# Gate_Driver_2.net
KiCad netlist of a schematic drawn in Altium Designer
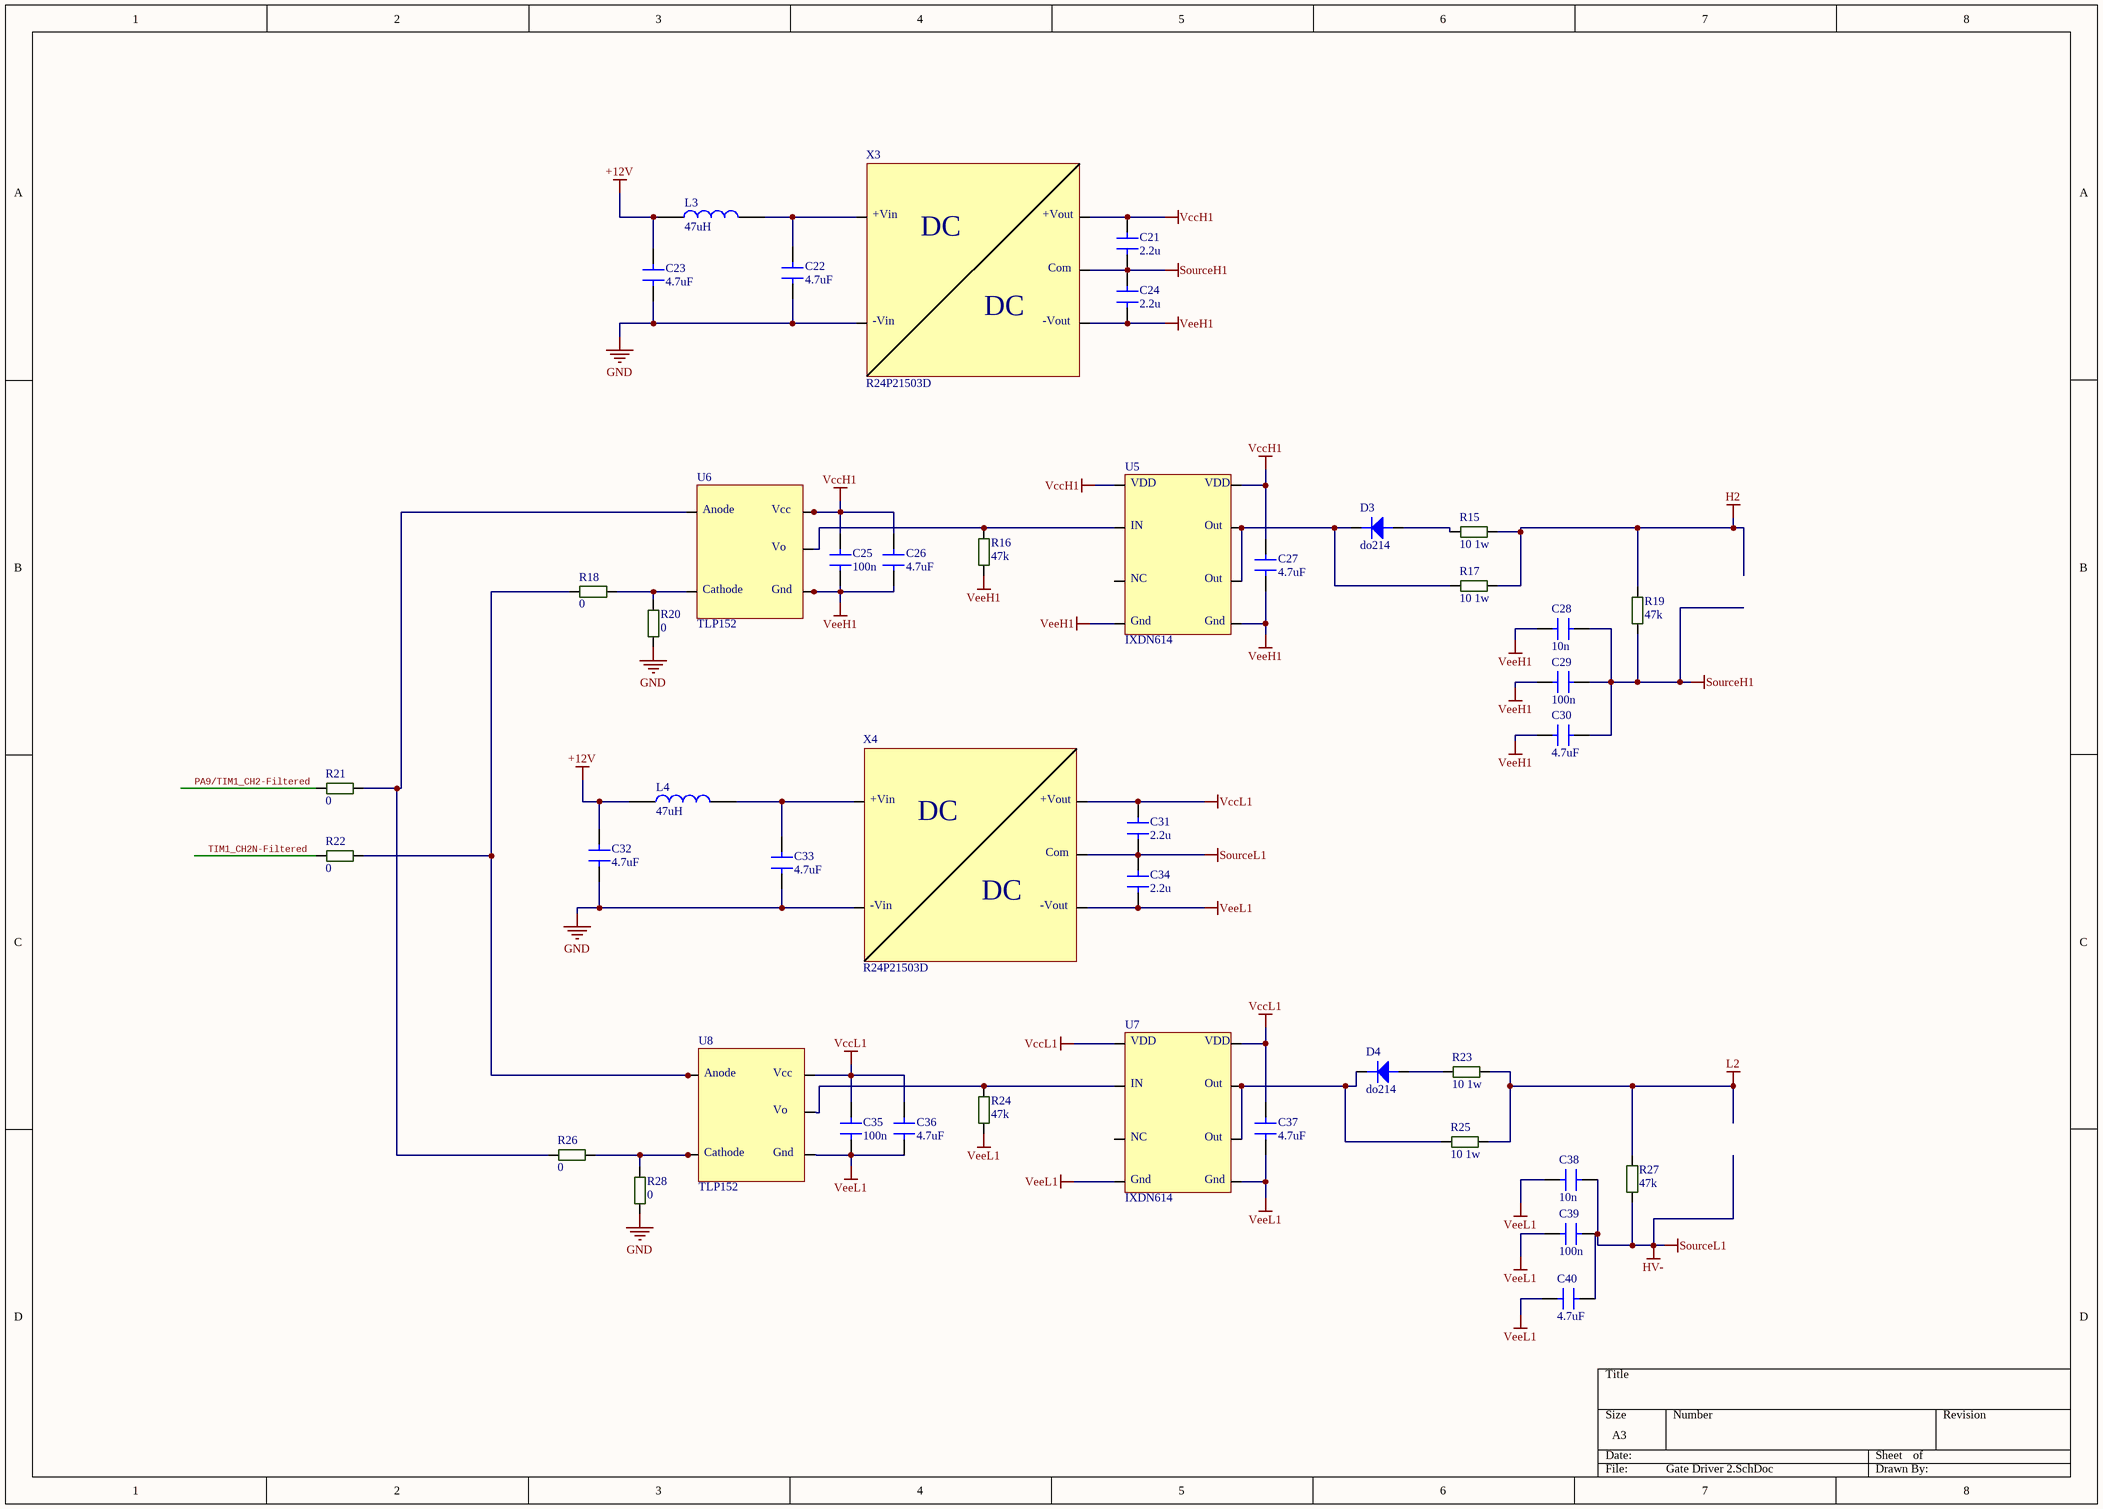
[diagram p0: Gate Driver 2.SchDoc]

(export (version "E")
  (design (tool "Eeschema 10.0.6"))
  (components
    (comp (ref "C21")
      (value "2.2u")
      (footprint "C-0805")
      (libsource (lib "Gate Driver Board") (part "C-0805"))
    )
    (comp (ref "C22")
      (value "4.7uF")
      (footprint "C-1206")
      (description "Cap1206 4.7uF")
      (fields (field (name "ÖZDISAN PART NUMBER") "CL31B475KBHNNNE") (field (name "MANUFACTURER") "SAMSUNG"))
      (libsource (lib "Gate Driver Board") (part "Cap1206"))
    )
    (comp (ref "C23")
      (value "4.7uF")
      (footprint "C-1206")
      (description "Cap1206 4.7uF")
      (fields (field (name "ÖZDISAN PART NUMBER") "CL31B475KBHNNNE") (field (name "MANUFACTURER") "SAMSUNG"))
      (libsource (lib "Gate Driver Board") (part "Cap1206"))
    )
    (comp (ref "C24")
      (value "2.2u")
      (footprint "C-0805")
      (libsource (lib "Gate Driver Board") (part "C-0805"))
    )
    (comp (ref "C25")
      (value "100n")
      (footprint "C-0805")
      (libsource (lib "Gate Driver Board") (part "C-0805"))
    )
    (comp (ref "C26")
      (value "4.7uF")
      (footprint "C-1206")
      (description "Cap1206 4.7uF")
      (libsource (lib "Gate Driver Board") (part "C-1206"))
    )
    (comp (ref "C27")
      (value "4.7uF")
      (footprint "C-1206")
      (description "Cap1206 4.7uF")
      (libsource (lib "Gate Driver Board") (part "C-1206"))
    )
    (comp (ref "C28")
      (value "10n")
      (footprint "C-0805")
      (libsource (lib "Gate Driver Board") (part "C-0805"))
    )
    (comp (ref "C29")
      (value "100n")
      (footprint "C-0805")
      (libsource (lib "Gate Driver Board") (part "C-0805"))
    )
    (comp (ref "C30")
      (value "4.7uF")
      (footprint "C-1206")
      (description "Cap1206 4.7uF")
      (fields (field (name "ÖZDISAN PART NUMBER") " CL31B475KBHNNNE") (field (name "MANUFACTURER") "SAMSUNG"))
      (libsource (lib "Gate Driver Board") (part "Cap1206"))
    )
    (comp (ref "C31")
      (value "2.2u")
      (footprint "C-0805")
      (libsource (lib "Gate Driver Board") (part "C-0805"))
    )
    (comp (ref "C32")
      (value "4.7uF")
      (footprint "C-1206")
      (description "Cap1206 4.7uF")
      (fields (field (name "ÖZDISAN PART NUMBER") "CL31B475KBHNNNE") (field (name "MANUFACTURER") "SAMSUNG"))
      (libsource (lib "Gate Driver Board") (part "Cap1206"))
    )
    (comp (ref "C33")
      (value "4.7uF")
      (footprint "C-1206")
      (description "Cap1206 4.7uF")
      (fields (field (name "ÖZDISAN PART NUMBER") " CL31B475KBHNNNE") (field (name "MANUFACTURER") "SAMSUNG"))
      (libsource (lib "Gate Driver Board") (part "Cap1206"))
    )
    (comp (ref "C34")
      (value "2.2u")
      (footprint "C-0805")
      (libsource (lib "Gate Driver Board") (part "C-0805"))
    )
    (comp (ref "C35")
      (value "100n")
      (footprint "C-0805")
      (libsource (lib "Gate Driver Board") (part "C-0805"))
    )
    (comp (ref "C36")
      (value "4.7uF")
      (footprint "C-1206")
      (description "Cap1206 4.7uF")
      (libsource (lib "Gate Driver Board") (part "C-1206"))
    )
    (comp (ref "C37")
      (value "4.7uF")
      (footprint "C-1206")
      (description "Cap1206 4.7uF")
      (libsource (lib "Gate Driver Board") (part "C-1206"))
    )
    (comp (ref "C38")
      (value "10n")
      (footprint "C-0805")
      (libsource (lib "Gate Driver Board") (part "C-0805"))
    )
    (comp (ref "C39")
      (value "100n")
      (footprint "C-0805")
      (libsource (lib "Gate Driver Board") (part "C-0805"))
    )
    (comp (ref "C40")
      (value "4.7uF")
      (footprint "C-1206")
      (description "Cap1206 4.7uF")
      (fields (field (name "ÖZDISAN PART NUMBER") "CL31B475KBHNNNE") (field (name "MANUFACTURER") "SAMSUNG"))
      (libsource (lib "Gate Driver Board") (part "Cap1206"))
    )
    (comp (ref "D3")
      (value "do214")
      (footprint "DO-214AC")
      (description "DIODE FAST SWITCHING Single 150mA 75V SMT SOD323")
      (libsource (lib "Gate Driver Board") (part "do214"))
    )
    (comp (ref "D4")
      (value "do214")
      (footprint "DO-214AC")
      (description "DIODE FAST SWITCHING Single 150mA 75V SMT SOD323")
      (libsource (lib "Gate Driver Board") (part "do214"))
    )
    (comp (ref "L3")
      (value "47uH")
      (footprint "WE-TPC_282892")
      (libsource (lib "Gate Driver Board") (part "inductor"))
    )
    (comp (ref "L4")
      (value "47uH")
      (footprint "WE-TPC_282892")
      (libsource (lib "Gate Driver Board") (part "inductor"))
    )
    (comp (ref "R15")
      (value "10 1w")
      (footprint "R-2512")
      (description "R-2512 10R 1W")
      (libsource (lib "Gate Driver Board") (part "R-2512"))
    )
    (comp (ref "R16")
      (value "47k")
      (footprint "R-0805")
      (description "RES.(2012) 0805 47K Ohms 5% 1/8W-S 100PPM")
      (fields (field (name "MANUFACTURER") "ROYALOHM") (field (name "ÖZDISAN PART NUMBER") "0805S8J0473T5E"))
      (libsource (lib "Gate Driver Board") (part "Res0805"))
    )
    (comp (ref "R17")
      (value "10 1w")
      (footprint "R-2512")
      (description "R-2512 10R 1W")
      (libsource (lib "Gate Driver Board") (part "R-2512"))
    )
    (comp (ref "R18")
      (value "0")
      (footprint "R-0805")
      (description "Res0805 0R")
      (fields (field (name "MANUFACTURER") "ROYALOHM") (field (name "ÖZDISAN PART NUMBER") "0805S8J0000T5E"))
      (libsource (lib "Gate Driver Board") (part "Res0805"))
    )
    (comp (ref "R19")
      (value "47k")
      (footprint "R-0805")
      (description "RES.(2012) 0805 47K Ohms 5% 1/8W-S 100PPM")
      (fields (field (name "ÖZDISAN PART NUMBER") "0805S8J0473T5E") (field (name "MANUFACTURER") "ROYALOHM"))
      (libsource (lib "Gate Driver Board") (part "Res0805"))
    )
    (comp (ref "R20")
      (value "0")
      (footprint "R-0805")
      (description "Res0805 0R")
      (fields (field (name "MANUFACTURER") "ROYALOHM") (field (name "ÖZDISAN PART NUMBER") "0805S8J0000T5E"))
      (libsource (lib "Gate Driver Board") (part "Res0805"))
    )
    (comp (ref "R21")
      (value "0")
      (footprint "R-0805")
      (description "Res0805 0R")
      (fields (field (name "MANUFACTURER") "ROYALOHM") (field (name "ÖZDISAN PART NUMBER") "0805S8J0000T5E"))
      (libsource (lib "Gate Driver Board") (part "Res0805"))
    )
    (comp (ref "R22")
      (value "0")
      (footprint "R-0805")
      (description "Res0805 0R")
      (fields (field (name "MANUFACTURER") "ROYALOHM") (field (name "ÖZDISAN PART NUMBER") "0805S8J0000T5E"))
      (libsource (lib "Gate Driver Board") (part "Res0805"))
    )
    (comp (ref "R23")
      (value "10 1w")
      (footprint "R-2512")
      (description "R-2512 10R 1W")
      (libsource (lib "Gate Driver Board") (part "R-2512"))
    )
    (comp (ref "R24")
      (value "47k")
      (footprint "R-0805")
      (description "RES.(2012) 0805 47K Ohms 5% 1/8W-S 100PPM")
      (fields (field (name "ÖZDISAN PART NUMBER") "0805S8J0473T5E") (field (name "MANUFACTURER") "ROYALOHM"))
      (libsource (lib "Gate Driver Board") (part "Res0805"))
    )
    (comp (ref "R25")
      (value "10 1w")
      (footprint "R-2512")
      (description "R-2512 10R 1W")
      (libsource (lib "Gate Driver Board") (part "R-2512"))
    )
    (comp (ref "R26")
      (value "0")
      (footprint "R-0805")
      (description "Res0805 0R")
      (fields (field (name "MANUFACTURER") "ROYALOHM") (field (name "ÖZDISAN PART NUMBER") "0805S8J0000T5E"))
      (libsource (lib "Gate Driver Board") (part "Res0805"))
    )
    (comp (ref "R27")
      (value "47k")
      (footprint "R-0805")
      (description "RES.(2012) 0805 47K Ohms 5% 1/8W-S 100PPM")
      (fields (field (name "ÖZDISAN PART NUMBER") "0805S8J0473T5E") (field (name "MANUFACTURER") "ROYALOHM"))
      (libsource (lib "Gate Driver Board") (part "Res0805"))
    )
    (comp (ref "R28")
      (value "0")
      (footprint "R-0805")
      (description "Res0805 0R")
      (fields (field (name "MANUFACTURER") "ROYALOHM") (field (name "ÖZDISAN PART NUMBER") "0805S8J0000T5E"))
      (libsource (lib "Gate Driver Board") (part "Res0805"))
    )
    (comp (ref "U5")
      (value "IXDN614")
      (footprint "FAN3122 Soic8")
      (description "14A 8SOIC EXP MTL NON INVERTING")
      (fields
        (field (name "MANUFACTURER") "Ixys Clare")
        (field (name "MANUFACTURER PART NUMBER") "IXDN614SITR")
      )
      (libsource (lib "Gate Driver Board") (part "IXDN614SITR"))
    )
    (comp (ref "U6")
      (value "TLP152")
      (footprint "TLP152")
      (description "OPTOISO 3.75KV GATE DRIVER 6SO-5")
      (fields
        (field (name "MANUFACTURER") "Toshiba")
        (field (name "MANUFACTURER PART NUMBER") "TLP152(TPL,E")
      )
      (libsource (lib "Gate Driver Board") (part "TLP152(TPL,E"))
    )
    (comp (ref "U7")
      (value "IXDN614")
      (footprint "FAN3122 Soic8")
      (description "14A 8SOIC EXP MTL NON INVERTING")
      (fields
        (field (name "MANUFACTURER") "Ixys Clare")
        (field (name "MANUFACTURER PART NUMBER") "IXDN614SITR")
      )
      (libsource (lib "Gate Driver Board") (part "IXDN614SITR"))
    )
    (comp (ref "U8")
      (value "TLP152")
      (footprint "TLP152")
      (description "OPTOISO 3.75KV GATE DRIVER 6SO-5")
      (fields
        (field (name "MANUFACTURER") "Toshiba")
        (field (name "MANUFACTURER PART NUMBER") "TLP152(TPL,E")
      )
      (libsource (lib "Gate Driver Board") (part "TLP152(TPL,E"))
    )
    (comp (ref "X3")
      (value "R24P21503D")
      (footprint "SIP7")
      (fields (field (name "MANUFACTURER") "Recom"))
      (libsource (lib "Gate Driver Board") (part "R24P21503D"))
    )
    (comp (ref "X4")
      (value "R24P21503D")
      (footprint "SIP7")
      (fields (field (name "MANUFACTURER") "Recom"))
      (libsource (lib "Gate Driver Board") (part "R24P21503D"))
    )
  )
  (nets
    (net (code "1") (name "+12V") (class "Default")
      (node (ref "C23") (pin "2") (pinfunction "2_2") (pintype "passive"))
      (node (ref "C32") (pin "2") (pinfunction "2_2") (pintype "passive"))
      (node (ref "L3") (pin "1") (pinfunction "1_1") (pintype "passive"))
      (node (ref "L4") (pin "1") (pinfunction "1_1") (pintype "passive"))
    )
    (net (code "2") (name "/PA9{slash}TIM1_CH2-Filtered") (class "Default")
      (node (ref "R21") (pin "1") (pinfunction "1_1") (pintype "passive"))
    )
    (net (code "3") (name "/TIM1_CH2N-Filtered") (class "Default")
      (node (ref "R22") (pin "1") (pinfunction "1_1") (pintype "passive"))
    )
    (net (code "4") (name "GND") (class "Default")
      (node (ref "C22") (pin "1") (pinfunction "1_1") (pintype "passive"))
      (node (ref "C23") (pin "1") (pinfunction "1_1") (pintype "passive"))
      (node (ref "C32") (pin "1") (pinfunction "1_1") (pintype "passive"))
      (node (ref "C33") (pin "1") (pinfunction "1_1") (pintype "passive"))
      (node (ref "R20") (pin "1") (pinfunction "1_1") (pintype "passive"))
      (node (ref "R28") (pin "1") (pinfunction "1_1") (pintype "passive"))
      (node (ref "X3") (pin "2") (pinfunction "2_2") (pintype "passive"))
      (node (ref "X4") (pin "2") (pinfunction "2_2") (pintype "passive"))
    )
    (net (code "5") (name "H2") (class "Default")
      (node (ref "R15") (pin "2") (pinfunction "2_2") (pintype "passive"))
      (node (ref "R17") (pin "2") (pinfunction "2_2") (pintype "passive"))
      (node (ref "R19") (pin "2") (pinfunction "2_2") (pintype "passive"))
    )
    (net (code "6") (name "HV-") (class "Default")
      (node (ref "C31") (pin "1") (pinfunction "1_1") (pintype "passive"))
      (node (ref "C34") (pin "2") (pinfunction "2_2") (pintype "passive"))
      (node (ref "C38") (pin "1") (pinfunction "1_1") (pintype "passive"))
      (node (ref "C39") (pin "1") (pinfunction "1_1") (pintype "passive"))
      (node (ref "C40") (pin "2") (pinfunction "2_2") (pintype "passive"))
      (node (ref "R27") (pin "1") (pinfunction "1_1") (pintype "passive"))
      (node (ref "X4") (pin "6") (pinfunction "6_6") (pintype "passive"))
    )
    (net (code "7") (name "L2") (class "Default")
      (node (ref "R23") (pin "2") (pinfunction "2_2") (pintype "passive"))
      (node (ref "R25") (pin "2") (pinfunction "2_2") (pintype "passive"))
      (node (ref "R27") (pin "2") (pinfunction "2_2") (pintype "passive"))
    )
    (net (code "8") (name "Net-(C22-Pad2)") (class "Default")
      (node (ref "C22") (pin "2") (pinfunction "2_2") (pintype "passive"))
      (node (ref "L3") (pin "2") (pinfunction "2_2") (pintype "passive"))
      (node (ref "X3") (pin "1") (pinfunction "1_1") (pintype "passive"))
    )
    (net (code "9") (name "Net-(C33-Pad2)") (class "Default")
      (node (ref "C33") (pin "2") (pinfunction "2_2") (pintype "passive"))
      (node (ref "L4") (pin "2") (pinfunction "2_2") (pintype "passive"))
      (node (ref "X4") (pin "1") (pinfunction "1_1") (pintype "passive"))
    )
    (net (code "10") (name "Net-(D3-Pada)") (class "Default")
      (node (ref "D3") (pin "a") (pinfunction "a_a") (pintype "passive"))
      (node (ref "R15") (pin "1") (pinfunction "1_1") (pintype "passive"))
    )
    (net (code "11") (name "Net-(D3-Padk)") (class "Default")
      (node (ref "D3") (pin "k") (pinfunction "k_k") (pintype "passive"))
      (node (ref "R17") (pin "1") (pinfunction "1_1") (pintype "passive"))
      (node (ref "U5") (pin "6") (pinfunction "6_6") (pintype "passive"))
      (node (ref "U5") (pin "7") (pinfunction "7_7") (pintype "passive"))
    )
    (net (code "12") (name "Net-(D4-Pada)") (class "Default")
      (node (ref "D4") (pin "a") (pinfunction "a_a") (pintype "passive"))
      (node (ref "R23") (pin "1") (pinfunction "1_1") (pintype "passive"))
    )
    (net (code "13") (name "Net-(D4-Padk)") (class "Default")
      (node (ref "D4") (pin "k") (pinfunction "k_k") (pintype "passive"))
      (node (ref "R25") (pin "1") (pinfunction "1_1") (pintype "passive"))
      (node (ref "U7") (pin "6") (pinfunction "6_6") (pintype "passive"))
      (node (ref "U7") (pin "7") (pinfunction "7_7") (pintype "passive"))
    )
    (net (code "14") (name "Net-(R16-Pad2)") (class "Default")
      (node (ref "R16") (pin "2") (pinfunction "2_2") (pintype "passive"))
      (node (ref "U5") (pin "2") (pinfunction "2_2") (pintype "passive"))
      (node (ref "U6") (pin "4") (pinfunction "4_4") (pintype "passive"))
    )
    (net (code "15") (name "Net-(R18-Pad1)") (class "Default")
      (node (ref "R18") (pin "1") (pinfunction "1_1") (pintype "passive"))
      (node (ref "R22") (pin "2") (pinfunction "2_2") (pintype "passive"))
      (node (ref "U8") (pin "1") (pinfunction "1_1") (pintype "passive"))
    )
    (net (code "16") (name "Net-(R18-Pad2)") (class "Default")
      (node (ref "R18") (pin "2") (pinfunction "2_2") (pintype "passive"))
      (node (ref "R20") (pin "2") (pinfunction "2_2") (pintype "passive"))
      (node (ref "U6") (pin "2") (pinfunction "2_2") (pintype "passive"))
    )
    (net (code "17") (name "Net-(R21-Pad2)") (class "Default")
      (node (ref "R21") (pin "2") (pinfunction "2_2") (pintype "passive"))
      (node (ref "R26") (pin "1") (pinfunction "1_1") (pintype "passive"))
      (node (ref "U6") (pin "1") (pinfunction "1_1") (pintype "passive"))
    )
    (net (code "18") (name "Net-(R24-Pad2)") (class "Default")
      (node (ref "R24") (pin "2") (pinfunction "2_2") (pintype "passive"))
      (node (ref "U7") (pin "2") (pinfunction "2_2") (pintype "passive"))
      (node (ref "U8") (pin "4") (pinfunction "4_4") (pintype "passive"))
    )
    (net (code "19") (name "Net-(R26-Pad2)") (class "Default")
      (node (ref "R26") (pin "2") (pinfunction "2_2") (pintype "passive"))
      (node (ref "R28") (pin "2") (pinfunction "2_2") (pintype "passive"))
      (node (ref "U8") (pin "2") (pinfunction "2_2") (pintype "passive"))
    )
    (net (code "20") (name "SourceH1") (class "Default")
      (node (ref "C21") (pin "1") (pinfunction "1_1") (pintype "passive"))
      (node (ref "C24") (pin "2") (pinfunction "2_2") (pintype "passive"))
      (node (ref "C28") (pin "1") (pinfunction "1_1") (pintype "passive"))
      (node (ref "C29") (pin "1") (pinfunction "1_1") (pintype "passive"))
      (node (ref "C30") (pin "2") (pinfunction "2_2") (pintype "passive"))
      (node (ref "R19") (pin "1") (pinfunction "1_1") (pintype "passive"))
      (node (ref "X3") (pin "6") (pinfunction "6_6") (pintype "passive"))
    )
    (net (code "21") (name "VccH1") (class "Default")
      (node (ref "C21") (pin "2") (pinfunction "2_2") (pintype "passive"))
      (node (ref "C25") (pin "2") (pinfunction "2_2") (pintype "passive"))
      (node (ref "C26") (pin "2") (pinfunction "2_2") (pintype "passive"))
      (node (ref "C27") (pin "2") (pinfunction "2_2") (pintype "passive"))
      (node (ref "U5") (pin "1") (pinfunction "1_1") (pintype "passive"))
      (node (ref "U5") (pin "8") (pinfunction "8_8") (pintype "passive"))
      (node (ref "U6") (pin "5") (pinfunction "5_5") (pintype "passive"))
      (node (ref "X3") (pin "7") (pinfunction "7_7") (pintype "passive"))
    )
    (net (code "22") (name "VccL1") (class "Default")
      (node (ref "C31") (pin "2") (pinfunction "2_2") (pintype "passive"))
      (node (ref "C35") (pin "2") (pinfunction "2_2") (pintype "passive"))
      (node (ref "C36") (pin "2") (pinfunction "2_2") (pintype "passive"))
      (node (ref "C37") (pin "2") (pinfunction "2_2") (pintype "passive"))
      (node (ref "U7") (pin "1") (pinfunction "1_1") (pintype "passive"))
      (node (ref "U7") (pin "8") (pinfunction "8_8") (pintype "passive"))
      (node (ref "U8") (pin "5") (pinfunction "5_5") (pintype "passive"))
      (node (ref "X4") (pin "7") (pinfunction "7_7") (pintype "passive"))
    )
    (net (code "23") (name "VeeH1") (class "Default")
      (node (ref "C24") (pin "1") (pinfunction "1_1") (pintype "passive"))
      (node (ref "C25") (pin "1") (pinfunction "1_1") (pintype "passive"))
      (node (ref "C26") (pin "1") (pinfunction "1_1") (pintype "passive"))
      (node (ref "C27") (pin "1") (pinfunction "1_1") (pintype "passive"))
      (node (ref "C28") (pin "2") (pinfunction "2_2") (pintype "passive"))
      (node (ref "C29") (pin "2") (pinfunction "2_2") (pintype "passive"))
      (node (ref "C30") (pin "1") (pinfunction "1_1") (pintype "passive"))
      (node (ref "R16") (pin "1") (pinfunction "1_1") (pintype "passive"))
      (node (ref "U5") (pin "4") (pinfunction "4_4") (pintype "passive"))
      (node (ref "U5") (pin "5") (pinfunction "5_5") (pintype "passive"))
      (node (ref "U6") (pin "3") (pinfunction "3_3") (pintype "passive"))
      (node (ref "X3") (pin "5") (pinfunction "5_5") (pintype "passive"))
    )
    (net (code "24") (name "VeeL1") (class "Default")
      (node (ref "C34") (pin "1") (pinfunction "1_1") (pintype "passive"))
      (node (ref "C35") (pin "1") (pinfunction "1_1") (pintype "passive"))
      (node (ref "C36") (pin "1") (pinfunction "1_1") (pintype "passive"))
      (node (ref "C37") (pin "1") (pinfunction "1_1") (pintype "passive"))
      (node (ref "C38") (pin "2") (pinfunction "2_2") (pintype "passive"))
      (node (ref "C39") (pin "2") (pinfunction "2_2") (pintype "passive"))
      (node (ref "C40") (pin "1") (pinfunction "1_1") (pintype "passive"))
      (node (ref "R24") (pin "1") (pinfunction "1_1") (pintype "passive"))
      (node (ref "U7") (pin "4") (pinfunction "4_4") (pintype "passive"))
      (node (ref "U7") (pin "5") (pinfunction "5_5") (pintype "passive"))
      (node (ref "U8") (pin "3") (pinfunction "3_3") (pintype "passive"))
      (node (ref "X4") (pin "5") (pinfunction "5_5") (pintype "passive"))
    )
    (net (code "25") (name "unconnected-(U5-Pad3)") (class "Default")
      (node (ref "U5") (pin "3") (pinfunction "3_3") (pintype "passive"))
    )
    (net (code "26") (name "unconnected-(U7-Pad3)") (class "Default")
      (node (ref "U7") (pin "3") (pinfunction "3_3") (pintype "passive"))
    )
  )
)
